# ChargerBase.net
KiCad netlist of a schematic drawn in EAGLE
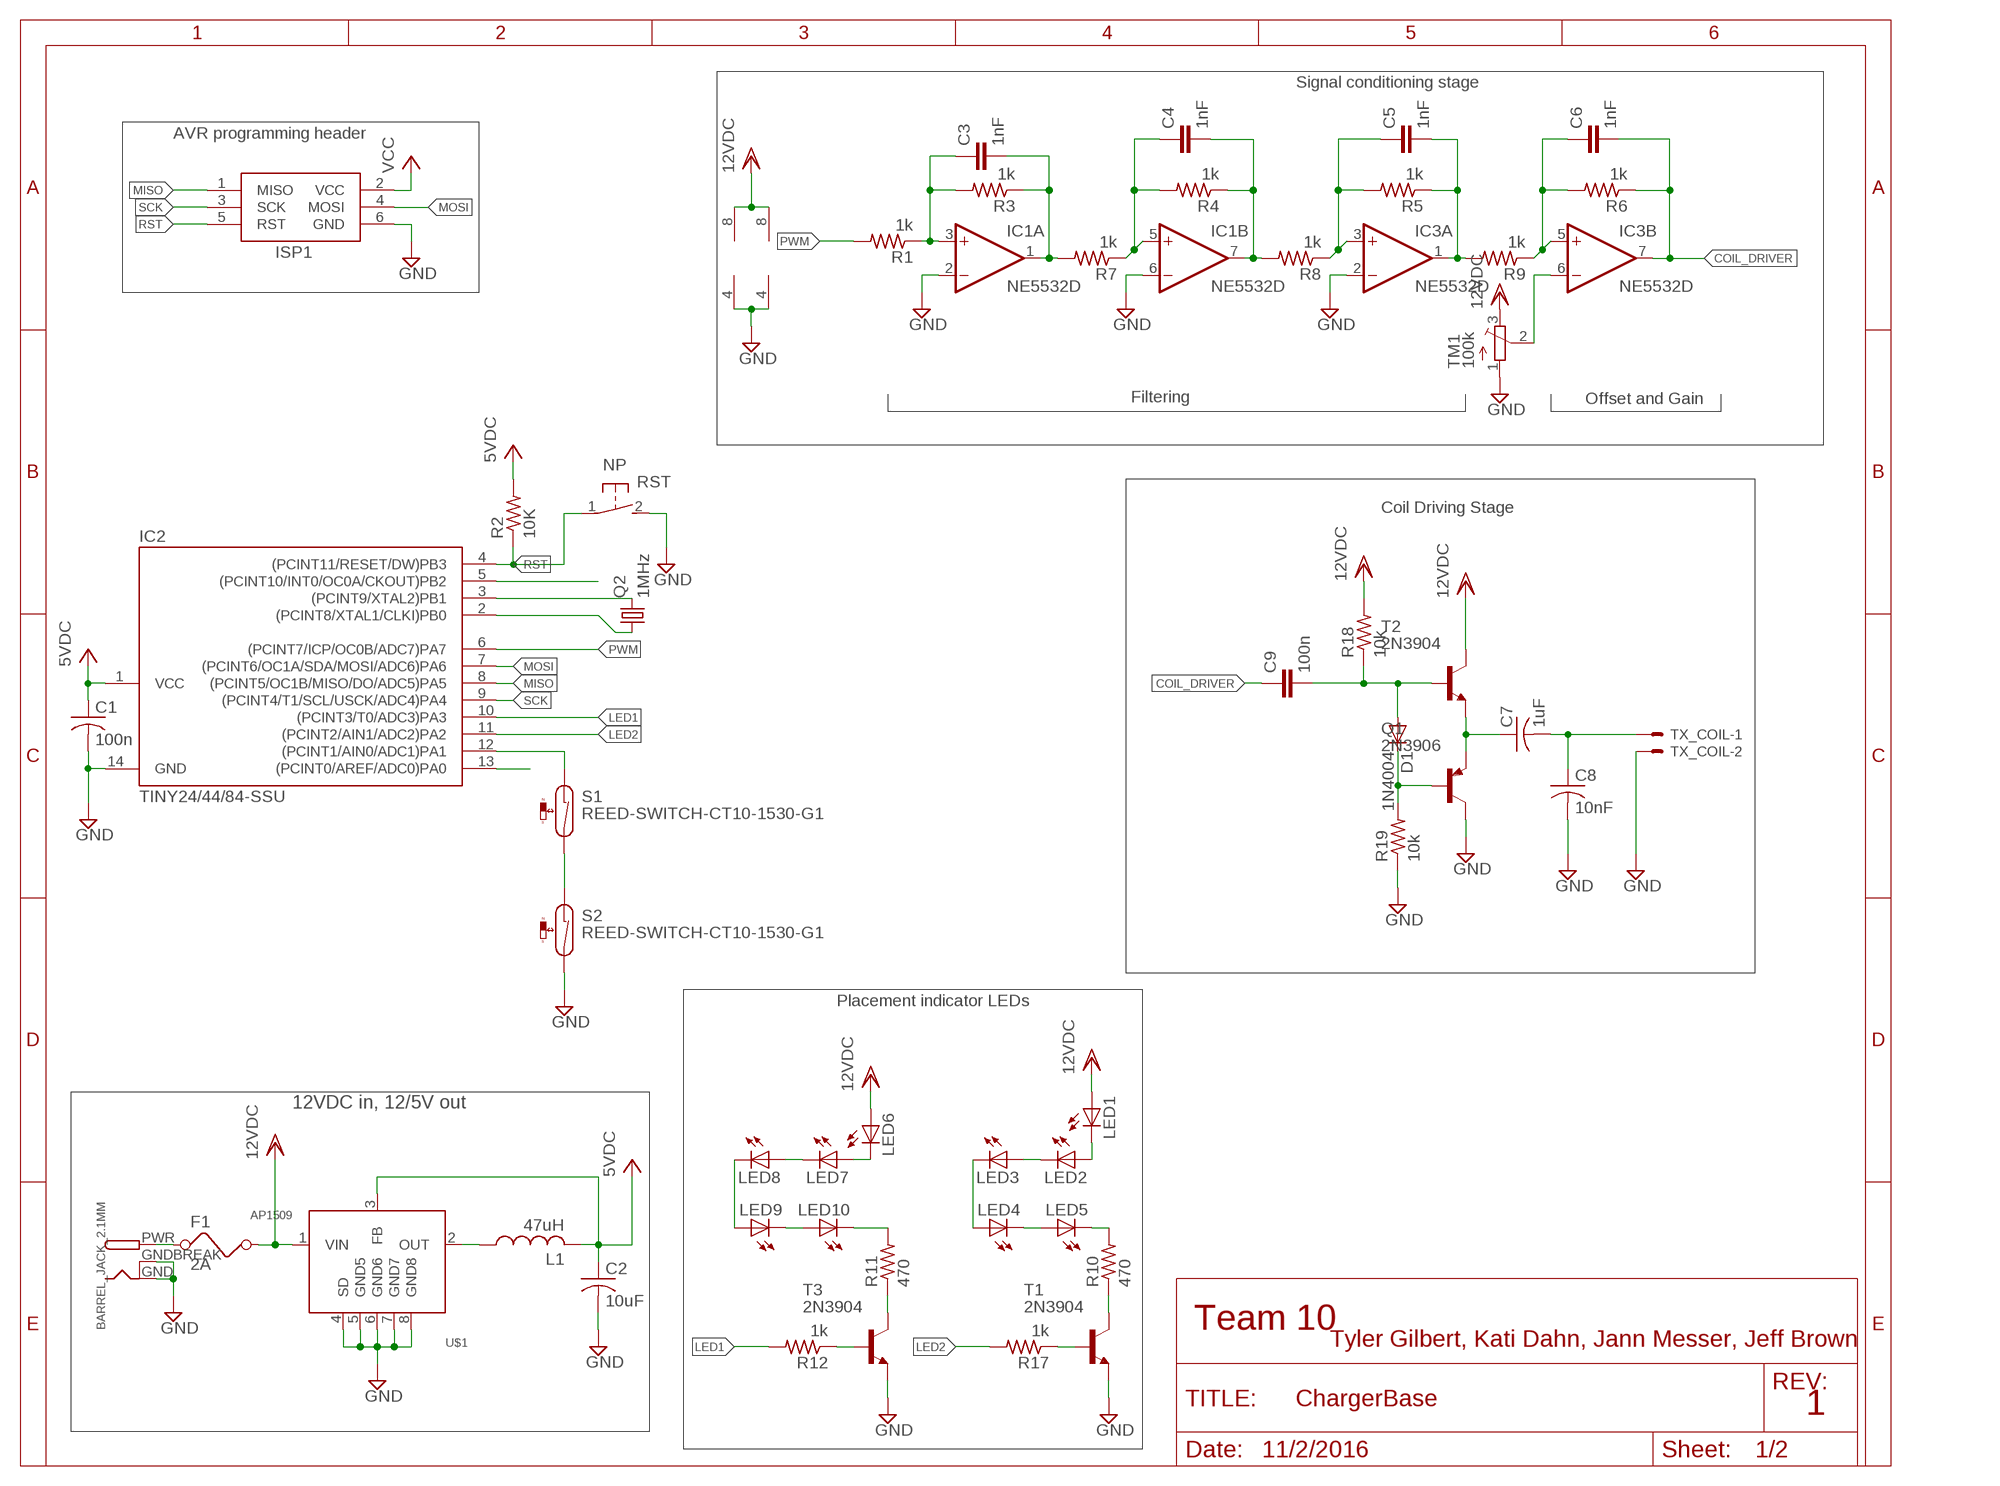
[diagram p0: schematic, sheet 1]

(export (version "E")
  (design (tool "Eeschema 10.0.6"))
  (components
    (comp (ref "BARREL_JACK_2.1MM")
      (value "DCBARRELPTH")
      (footprint "eagle-import:DCJACK_2MM_PTH")
      (libsource (lib "eagle-import") (part "DCBARRELPTH"))
    )
    (comp (ref "C1")
      (value "100n")
      (footprint "eagle-import:C0805")
      (libsource (lib "eagle-import") (part "rcl_C-USC0805"))
    )
    (comp (ref "C2")
      (value "10uF")
      (footprint "eagle-import:C025-040X050")
      (libsource (lib "eagle-import") (part "C-US025-040X050"))
    )
    (comp (ref "C3")
      (value "1nF")
      (footprint "eagle-import:C0805")
      (libsource (lib "eagle-import") (part "C-EUC0805"))
    )
    (comp (ref "C4")
      (value "1nF")
      (footprint "eagle-import:C0805")
      (libsource (lib "eagle-import") (part "C-EUC0805"))
    )
    (comp (ref "C5")
      (value "1nF")
      (footprint "eagle-import:C0805")
      (libsource (lib "eagle-import") (part "C-EUC0805"))
    )
    (comp (ref "C6")
      (value "1nF")
      (footprint "eagle-import:C0805")
      (libsource (lib "eagle-import") (part "C-EUC0805"))
    )
    (comp (ref "C7")
      (value "1uF")
      (footprint "eagle-import:C050-025X075")
      (libsource (lib "eagle-import") (part "C-US050-025X075"))
    )
    (comp (ref "C8")
      (value "10nF")
      (footprint "eagle-import:C050-025X075")
      (libsource (lib "eagle-import") (part "C-US050-025X075"))
    )
    (comp (ref "C9")
      (value "100n")
      (footprint "eagle-import:C0805")
      (libsource (lib "eagle-import") (part "C-EUC0805"))
    )
    (comp (ref "D1")
      (value "1N4004")
      (footprint "eagle-import:DO41-10")
      (libsource (lib "eagle-import") (part "1N4004"))
    )
    (comp (ref "F1")
      (value "2A")
      (footprint "eagle-import:FUSE")
      (libsource (lib "eagle-import") (part "FUSE"))
    )
    (comp (ref "IC1")
      (value "NE5532D")
      (footprint "eagle-import:SO08")
      (libsource (lib "eagle-import") (part "NE5532D"))
    )
    (comp (ref "IC2")
      (value "TINY24/44/84-SSU")
      (footprint "eagle-import:SOIC14")
      (libsource (lib "eagle-import") (part "TINY24/44/84-SSU"))
    )
    (comp (ref "IC3")
      (value "NE5532D")
      (footprint "eagle-import:SO08")
      (libsource (lib "eagle-import") (part "NE5532D"))
    )
    (comp (ref "ISP1")
      (value "AVRISP-6")
      (footprint "eagle-import:AVRISP")
      (libsource (lib "eagle-import") (part "AVRISP-6"))
    )
    (comp (ref "L1")
      (value "47uH")
      (footprint "eagle-import:0207_7")
      (libsource (lib "eagle-import") (part "L-US0207/7"))
    )
    (comp (ref "LED1")
      (value "LEDCHIPLED_0805")
      (footprint "eagle-import:CHIPLED_0805")
      (libsource (lib "eagle-import") (part "LEDCHIPLED_0805"))
    )
    (comp (ref "LED2")
      (value "LEDCHIPLED_0805")
      (footprint "eagle-import:CHIPLED_0805")
      (libsource (lib "eagle-import") (part "LEDCHIPLED_0805"))
    )
    (comp (ref "LED3")
      (value "LEDCHIPLED_0805")
      (footprint "eagle-import:CHIPLED_0805")
      (libsource (lib "eagle-import") (part "LEDCHIPLED_0805"))
    )
    (comp (ref "LED4")
      (value "LEDCHIPLED_0805")
      (footprint "eagle-import:CHIPLED_0805")
      (libsource (lib "eagle-import") (part "LEDCHIPLED_0805"))
    )
    (comp (ref "LED5")
      (value "LEDCHIPLED_0805")
      (footprint "eagle-import:CHIPLED_0805")
      (libsource (lib "eagle-import") (part "LEDCHIPLED_0805"))
    )
    (comp (ref "LED6")
      (value "LEDCHIPLED_0805")
      (footprint "eagle-import:CHIPLED_0805")
      (libsource (lib "eagle-import") (part "LEDCHIPLED_0805"))
    )
    (comp (ref "LED7")
      (value "LEDCHIPLED_0805")
      (footprint "eagle-import:CHIPLED_0805")
      (libsource (lib "eagle-import") (part "LEDCHIPLED_0805"))
    )
    (comp (ref "LED8")
      (value "LEDCHIPLED_0805")
      (footprint "eagle-import:CHIPLED_0805")
      (libsource (lib "eagle-import") (part "LEDCHIPLED_0805"))
    )
    (comp (ref "LED9")
      (value "LEDCHIPLED_0805")
      (footprint "eagle-import:CHIPLED_0805")
      (libsource (lib "eagle-import") (part "LEDCHIPLED_0805"))
    )
    (comp (ref "LED10")
      (value "LEDCHIPLED_0805")
      (footprint "eagle-import:CHIPLED_0805")
      (libsource (lib "eagle-import") (part "LEDCHIPLED_0805"))
    )
    (comp (ref "NP")
      (value "RST")
      (footprint "eagle-import:DTSM-3")
      (libsource (lib "eagle-import") (part "DTSM-3"))
    )
    (comp (ref "Q1")
      (value "2N3906")
      (footprint "eagle-import:TO92")
      (libsource (lib "eagle-import") (part "2N3906"))
    )
    (comp (ref "Q2")
      (value "1MHz")
      (footprint "eagle-import:SM49")
      (libsource (lib "eagle-import") (part "CRYSTALSM49"))
    )
    (comp (ref "R1")
      (value "1k")
      (footprint "eagle-import:R0805")
      (libsource (lib "eagle-import") (part "R-US_R0805"))
    )
    (comp (ref "R2")
      (value "10K")
      (footprint "eagle-import:R0805")
      (libsource (lib "eagle-import") (part "R-US_R0805"))
    )
    (comp (ref "R3")
      (value "1k")
      (footprint "eagle-import:R0805")
      (libsource (lib "eagle-import") (part "R-US_R0805"))
    )
    (comp (ref "R4")
      (value "1k")
      (footprint "eagle-import:R0805")
      (libsource (lib "eagle-import") (part "R-US_R0805"))
    )
    (comp (ref "R5")
      (value "1k")
      (footprint "eagle-import:R0805")
      (libsource (lib "eagle-import") (part "R-US_R0805"))
    )
    (comp (ref "R6")
      (value "1k")
      (footprint "eagle-import:R0805")
      (libsource (lib "eagle-import") (part "R-US_R0805"))
    )
    (comp (ref "R7")
      (value "1k")
      (footprint "eagle-import:R0805")
      (libsource (lib "eagle-import") (part "R-US_R0805"))
    )
    (comp (ref "R8")
      (value "1k")
      (footprint "eagle-import:R0805")
      (libsource (lib "eagle-import") (part "R-US_R0805"))
    )
    (comp (ref "R9")
      (value "1k")
      (footprint "eagle-import:R0805")
      (libsource (lib "eagle-import") (part "R-US_R0805"))
    )
    (comp (ref "R10")
      (value "470")
      (footprint "eagle-import:R0805")
      (libsource (lib "eagle-import") (part "R-US_R0805"))
    )
    (comp (ref "R11")
      (value "470")
      (footprint "eagle-import:R0805")
      (libsource (lib "eagle-import") (part "R-US_R0805"))
    )
    (comp (ref "R12")
      (value "1k")
      (footprint "eagle-import:R0805")
      (libsource (lib "eagle-import") (part "R-US_R0805"))
    )
    (comp (ref "R17")
      (value "1k")
      (footprint "eagle-import:R0805")
      (libsource (lib "eagle-import") (part "R-US_R0805"))
    )
    (comp (ref "R18")
      (value "10k")
      (footprint "eagle-import:R0805")
      (libsource (lib "eagle-import") (part "R-US_R0805"))
    )
    (comp (ref "R19")
      (value "10k")
      (footprint "eagle-import:R0805")
      (libsource (lib "eagle-import") (part "R-US_R0805"))
    )
    (comp (ref "S1")
      (value "REED-SWITCH-CT10-1530-G1")
      (footprint "eagle-import:CT10-G1")
      (fields (field (name "MF") "COTO TECHNOLOGY") (field (name "MPN") "CT10-1530-G1"))
      (libsource (lib "eagle-import") (part "REED-SWITCH-CT10-1530-G1"))
    )
    (comp (ref "S2")
      (value "REED-SWITCH-CT10-1530-G1")
      (footprint "eagle-import:CT10-G1")
      (fields (field (name "MF") "COTO TECHNOLOGY") (field (name "MPN") "CT10-1530-G1"))
      (libsource (lib "eagle-import") (part "REED-SWITCH-CT10-1530-G1"))
    )
    (comp (ref "T1")
      (value "2N3904")
      (footprint "eagle-import:TO92")
      (libsource (lib "eagle-import") (part "2N3904"))
    )
    (comp (ref "T2")
      (value "2N3904")
      (footprint "eagle-import:TO92")
      (libsource (lib "eagle-import") (part "2N3904"))
    )
    (comp (ref "T3")
      (value "2N3904")
      (footprint "eagle-import:TO92")
      (libsource (lib "eagle-import") (part "2N3904"))
    )
    (comp (ref "TM1")
      (value "100k")
      (footprint "eagle-import:TC33X")
      (libsource (lib "eagle-import") (part "TRIMPOTTC33X"))
    )
    (comp (ref "TX_COIL")
      (value "22-23-2021")
      (footprint "eagle-import:22-23-2021")
      (fields (field (name "MF") "MOLEX"))
      (libsource (lib "eagle-import") (part "22-23-2021"))
    )
    (comp (ref "U$1")
      (value "AP1509")
      (footprint "eagle-import:SOP08")
      (libsource (lib "eagle-import") (part "AP1509"))
    )
  )
  (nets
    (net (code "1") (name "5VDC") (class "Default")
      (node (ref "C1") (pin "1") (pinfunction "1_1") (pintype "passive"))
      (node (ref "C2") (pin "1") (pinfunction "1_1") (pintype "passive"))
      (node (ref "IC2") (pin "1") (pinfunction "VCC_1") (pintype "power_in"))
      (node (ref "ISP1") (pin "2") (pinfunction "VCC_2") (pintype "power_in"))
      (node (ref "L1") (pin "2") (pinfunction "2_2") (pintype "passive"))
      (node (ref "R2") (pin "2") (pinfunction "2_2") (pintype "passive"))
      (node (ref "U$1") (pin "3") (pinfunction "FB_3") (pintype "bidirectional"))
    )
    (net (code "2") (name "12VDC") (class "Default")
      (node (ref "F1") (pin "2") (pinfunction "2_2") (pintype "passive"))
      (node (ref "IC1") (pin "8") (pinfunction "V+_8") (pintype "power_in"))
      (node (ref "IC3") (pin "8") (pinfunction "V+_8") (pintype "power_in"))
      (node (ref "LED1") (pin "A") (pinfunction "A_A") (pintype "passive"))
      (node (ref "LED6") (pin "A") (pinfunction "A_A") (pintype "passive"))
      (node (ref "R18") (pin "2") (pinfunction "2_2") (pintype "passive"))
      (node (ref "T2") (pin "1") (pinfunction "C_1") (pintype "passive"))
      (node (ref "TM1") (pin "3") (pinfunction "E_3") (pintype "passive"))
      (node (ref "U$1") (pin "1") (pinfunction "VIN_1") (pintype "bidirectional"))
    )
    (net (code "3") (name "COIL_DRIVER") (class "Default")
      (node (ref "C6") (pin "2") (pinfunction "2_2") (pintype "passive"))
      (node (ref "C9") (pin "1") (pinfunction "1_1") (pintype "passive"))
      (node (ref "IC3") (pin "7") (pinfunction "OUT_7") (pintype "output"))
      (node (ref "R6") (pin "1") (pinfunction "1_1") (pintype "passive"))
    )
    (net (code "4") (name "GND") (class "Default")
      (node (ref "BARREL_JACK_2.1MM") (pin "GND") (pinfunction "GND_GND") (pintype "power_in"))
      (node (ref "BARREL_JACK_2.1MM") (pin "GNDBREAK") (pinfunction "GNDBREAK_GNDBREAK") (pintype "power_in"))
      (node (ref "C1") (pin "2") (pinfunction "2_2") (pintype "passive"))
      (node (ref "C2") (pin "2") (pinfunction "2_2") (pintype "passive"))
      (node (ref "C8") (pin "2") (pinfunction "2_2") (pintype "passive"))
      (node (ref "IC1") (pin "2") (pinfunction "-IN_2") (pintype "input"))
      (node (ref "IC1") (pin "4") (pinfunction "V-_4") (pintype "power_in"))
      (node (ref "IC1") (pin "6") (pinfunction "-IN_6") (pintype "input"))
      (node (ref "IC2") (pin "14") (pinfunction "GND_14") (pintype "power_in"))
      (node (ref "IC3") (pin "2") (pinfunction "-IN_2") (pintype "input"))
      (node (ref "IC3") (pin "4") (pinfunction "V-_4") (pintype "power_in"))
      (node (ref "ISP1") (pin "6") (pinfunction "GND_6") (pintype "power_in"))
      (node (ref "NP") (pin "2") (pinfunction "2_2") (pintype "passive"))
      (node (ref "Q1") (pin "1") (pinfunction "C_1") (pintype "passive"))
      (node (ref "R19") (pin "1") (pinfunction "1_1") (pintype "passive"))
      (node (ref "S2") (pin "2") (pinfunction "2_2") (pintype "passive"))
      (node (ref "T1") (pin "3") (pinfunction "E_3") (pintype "passive"))
      (node (ref "T3") (pin "3") (pinfunction "E_3") (pintype "passive"))
      (node (ref "TM1") (pin "1") (pinfunction "A_1") (pintype "passive"))
      (node (ref "TX_COIL") (pin "2") (pinfunction "S_2") (pintype "passive"))
      (node (ref "U$1") (pin "4") (pinfunction "SD_4") (pintype "bidirectional"))
      (node (ref "U$1") (pin "5") (pinfunction "GND5_5") (pintype "bidirectional"))
      (node (ref "U$1") (pin "6") (pinfunction "GND6_6") (pintype "bidirectional"))
      (node (ref "U$1") (pin "7") (pinfunction "GND7_7") (pintype "bidirectional"))
      (node (ref "U$1") (pin "8") (pinfunction "GND8_8") (pintype "bidirectional"))
    )
    (net (code "5") (name "LED1") (class "Default")
      (node (ref "IC2") (pin "10") (pinfunction "(PCINT3/T0/ADC3)PA3_10") (pintype "bidirectional"))
      (node (ref "R12") (pin "2") (pinfunction "2_2") (pintype "passive"))
    )
    (net (code "6") (name "LED2") (class "Default")
      (node (ref "IC2") (pin "11") (pinfunction "(PCINT2/AIN1/ADC2)PA2_11") (pintype "bidirectional"))
      (node (ref "R17") (pin "2") (pinfunction "2_2") (pintype "passive"))
    )
    (net (code "7") (name "MISO") (class "Default")
      (node (ref "IC2") (pin "8") (pinfunction "(PCINT5/OC1B/MISO/DO/ADC5)PA5_8") (pintype "bidirectional"))
      (node (ref "ISP1") (pin "1") (pinfunction "MISO_1") (pintype "input"))
    )
    (net (code "8") (name "MOSI") (class "Default")
      (node (ref "IC2") (pin "7") (pinfunction "(PCINT6/OC1A/SDA/MOSI/ADC6)PA6_7") (pintype "bidirectional"))
      (node (ref "ISP1") (pin "4") (pinfunction "MOSI_4") (pintype "output"))
    )
    (net (code "9") (name "Net-(BARREL_JACK_2.1MM-PadPWR)") (class "Default")
      (node (ref "BARREL_JACK_2.1MM") (pin "PWR") (pinfunction "PWR_PWR") (pintype "power_in"))
      (node (ref "F1") (pin "1") (pinfunction "1_1") (pintype "passive"))
    )
    (net (code "10") (name "Net-(IC1A-+IN)") (class "Default")
      (node (ref "C3") (pin "1") (pinfunction "1_1") (pintype "passive"))
      (node (ref "IC1") (pin "3") (pinfunction "+IN_3") (pintype "input"))
      (node (ref "R1") (pin "1") (pinfunction "1_1") (pintype "passive"))
      (node (ref "R3") (pin "2") (pinfunction "2_2") (pintype "passive"))
    )
    (net (code "11") (name "Net-(IC1A-OUT)") (class "Default")
      (node (ref "C3") (pin "2") (pinfunction "2_2") (pintype "passive"))
      (node (ref "IC1") (pin "1") (pinfunction "OUT_1") (pintype "output"))
      (node (ref "R3") (pin "1") (pinfunction "1_1") (pintype "passive"))
      (node (ref "R7") (pin "2") (pinfunction "2_2") (pintype "passive"))
    )
    (net (code "12") (name "Net-(IC1B-+IN)") (class "Default")
      (node (ref "C4") (pin "1") (pinfunction "1_1") (pintype "passive"))
      (node (ref "IC1") (pin "5") (pinfunction "+IN_5") (pintype "input"))
      (node (ref "R4") (pin "2") (pinfunction "2_2") (pintype "passive"))
      (node (ref "R7") (pin "1") (pinfunction "1_1") (pintype "passive"))
    )
    (net (code "13") (name "Net-(IC1B-OUT)") (class "Default")
      (node (ref "C4") (pin "2") (pinfunction "2_2") (pintype "passive"))
      (node (ref "IC1") (pin "7") (pinfunction "OUT_7") (pintype "output"))
      (node (ref "R4") (pin "1") (pinfunction "1_1") (pintype "passive"))
      (node (ref "R8") (pin "2") (pinfunction "2_2") (pintype "passive"))
    )
    (net (code "14") (name "Net-(IC2-(PCINT1{slash}AIN0{slash}ADC1)PA1)") (class "Default")
      (node (ref "IC2") (pin "12") (pinfunction "(PCINT1/AIN0/ADC1)PA1_12") (pintype "bidirectional"))
      (node (ref "S1") (pin "1") (pinfunction "1_1") (pintype "passive"))
    )
    (net (code "15") (name "Net-(IC2-(PCINT8{slash}XTAL1{slash}CLKI)PB0)") (class "Default")
      (node (ref "IC2") (pin "2") (pinfunction "(PCINT8/XTAL1/CLKI)PB0_2") (pintype "bidirectional"))
      (node (ref "Q2") (pin "1") (pinfunction "1_1") (pintype "passive"))
    )
    (net (code "16") (name "Net-(IC2-(PCINT9{slash}XTAL2)PB1)") (class "Default")
      (node (ref "IC2") (pin "3") (pinfunction "(PCINT9/XTAL2)PB1_3") (pintype "bidirectional"))
      (node (ref "Q2") (pin "2") (pinfunction "2_2") (pintype "passive"))
    )
    (net (code "17") (name "Net-(IC3A-+IN)") (class "Default")
      (node (ref "C5") (pin "1") (pinfunction "1_1") (pintype "passive"))
      (node (ref "IC3") (pin "3") (pinfunction "+IN_3") (pintype "input"))
      (node (ref "R5") (pin "2") (pinfunction "2_2") (pintype "passive"))
      (node (ref "R8") (pin "1") (pinfunction "1_1") (pintype "passive"))
    )
    (net (code "18") (name "Net-(IC3A-OUT)") (class "Default")
      (node (ref "C5") (pin "2") (pinfunction "2_2") (pintype "passive"))
      (node (ref "IC3") (pin "1") (pinfunction "OUT_1") (pintype "output"))
      (node (ref "R5") (pin "1") (pinfunction "1_1") (pintype "passive"))
      (node (ref "R9") (pin "2") (pinfunction "2_2") (pintype "passive"))
    )
    (net (code "19") (name "Net-(IC3B-+IN)") (class "Default")
      (node (ref "C6") (pin "1") (pinfunction "1_1") (pintype "passive"))
      (node (ref "IC3") (pin "5") (pinfunction "+IN_5") (pintype "input"))
      (node (ref "R6") (pin "2") (pinfunction "2_2") (pintype "passive"))
      (node (ref "R9") (pin "1") (pinfunction "1_1") (pintype "passive"))
    )
    (net (code "20") (name "Net-(IC3B--IN)") (class "Default")
      (node (ref "IC3") (pin "6") (pinfunction "-IN_6") (pintype "input"))
      (node (ref "TM1") (pin "2") (pinfunction "S_2") (pintype "passive"))
    )
    (net (code "21") (name "Net-(LED1-PadC)") (class "Default")
      (node (ref "LED1") (pin "C") (pinfunction "C_C") (pintype "passive"))
      (node (ref "LED2") (pin "A") (pinfunction "A_A") (pintype "passive"))
    )
    (net (code "22") (name "Net-(LED2-PadC)") (class "Default")
      (node (ref "LED2") (pin "C") (pinfunction "C_C") (pintype "passive"))
      (node (ref "LED3") (pin "A") (pinfunction "A_A") (pintype "passive"))
    )
    (net (code "23") (name "Net-(LED3-PadC)") (class "Default")
      (node (ref "LED3") (pin "C") (pinfunction "C_C") (pintype "passive"))
      (node (ref "LED4") (pin "A") (pinfunction "A_A") (pintype "passive"))
    )
    (net (code "24") (name "Net-(LED4-PadC)") (class "Default")
      (node (ref "LED4") (pin "C") (pinfunction "C_C") (pintype "passive"))
      (node (ref "LED5") (pin "A") (pinfunction "A_A") (pintype "passive"))
    )
    (net (code "25") (name "Net-(LED5-PadC)") (class "Default")
      (node (ref "LED5") (pin "C") (pinfunction "C_C") (pintype "passive"))
      (node (ref "R10") (pin "2") (pinfunction "2_2") (pintype "passive"))
    )
    (net (code "26") (name "Net-(LED6-PadC)") (class "Default")
      (node (ref "LED6") (pin "C") (pinfunction "C_C") (pintype "passive"))
      (node (ref "LED7") (pin "A") (pinfunction "A_A") (pintype "passive"))
    )
    (net (code "27") (name "Net-(LED7-PadC)") (class "Default")
      (node (ref "LED7") (pin "C") (pinfunction "C_C") (pintype "passive"))
      (node (ref "LED8") (pin "A") (pinfunction "A_A") (pintype "passive"))
    )
    (net (code "28") (name "Net-(LED8-PadC)") (class "Default")
      (node (ref "LED8") (pin "C") (pinfunction "C_C") (pintype "passive"))
      (node (ref "LED9") (pin "A") (pinfunction "A_A") (pintype "passive"))
    )
    (net (code "29") (name "Net-(LED10-PadA)") (class "Default")
      (node (ref "LED10") (pin "A") (pinfunction "A_A") (pintype "passive"))
      (node (ref "LED9") (pin "C") (pinfunction "C_C") (pintype "passive"))
    )
    (net (code "30") (name "Net-(LED10-PadC)") (class "Default")
      (node (ref "LED10") (pin "C") (pinfunction "C_C") (pintype "passive"))
      (node (ref "R11") (pin "2") (pinfunction "2_2") (pintype "passive"))
    )
    (net (code "31") (name "Net-(Q1-B)") (class "Default")
      (node (ref "D1") (pin "C") (pinfunction "C_C") (pintype "passive"))
      (node (ref "Q1") (pin "2") (pinfunction "B_2") (pintype "passive"))
      (node (ref "R19") (pin "2") (pinfunction "2_2") (pintype "passive"))
    )
    (net (code "32") (name "Net-(Q1-E)") (class "Default")
      (node (ref "C7") (pin "1") (pinfunction "1_1") (pintype "passive"))
      (node (ref "Q1") (pin "3") (pinfunction "E_3") (pintype "passive"))
      (node (ref "T2") (pin "3") (pinfunction "E_3") (pintype "passive"))
    )
    (net (code "33") (name "Net-(S1-Pad2)") (class "Default")
      (node (ref "S1") (pin "2") (pinfunction "2_2") (pintype "passive"))
      (node (ref "S2") (pin "1") (pinfunction "1_1") (pintype "passive"))
    )
    (net (code "34") (name "Net-(T1-B)") (class "Default")
      (node (ref "R17") (pin "1") (pinfunction "1_1") (pintype "passive"))
      (node (ref "T1") (pin "2") (pinfunction "B_2") (pintype "passive"))
    )
    (net (code "35") (name "Net-(T1-C)") (class "Default")
      (node (ref "R10") (pin "1") (pinfunction "1_1") (pintype "passive"))
      (node (ref "T1") (pin "1") (pinfunction "C_1") (pintype "passive"))
    )
    (net (code "36") (name "Net-(T2-B)") (class "Default")
      (node (ref "C9") (pin "2") (pinfunction "2_2") (pintype "passive"))
      (node (ref "D1") (pin "A") (pinfunction "A_A") (pintype "passive"))
      (node (ref "R18") (pin "1") (pinfunction "1_1") (pintype "passive"))
      (node (ref "T2") (pin "2") (pinfunction "B_2") (pintype "passive"))
    )
    (net (code "37") (name "Net-(T3-B)") (class "Default")
      (node (ref "R12") (pin "1") (pinfunction "1_1") (pintype "passive"))
      (node (ref "T3") (pin "2") (pinfunction "B_2") (pintype "passive"))
    )
    (net (code "38") (name "Net-(T3-C)") (class "Default")
      (node (ref "R11") (pin "1") (pinfunction "1_1") (pintype "passive"))
      (node (ref "T3") (pin "1") (pinfunction "C_1") (pintype "passive"))
    )
    (net (code "39") (name "Net-(TX_COILA-S)") (class "Default")
      (node (ref "C7") (pin "2") (pinfunction "2_2") (pintype "passive"))
      (node (ref "C8") (pin "1") (pinfunction "1_1") (pintype "passive"))
      (node (ref "TX_COIL") (pin "1") (pinfunction "S_1") (pintype "passive"))
    )
    (net (code "40") (name "Net-(U$1-OUT)") (class "Default")
      (node (ref "L1") (pin "1") (pinfunction "1_1") (pintype "passive"))
      (node (ref "U$1") (pin "2") (pinfunction "OUT_2") (pintype "bidirectional"))
    )
    (net (code "41") (name "PWM") (class "Default")
      (node (ref "IC2") (pin "6") (pinfunction "(PCINT7/ICP/OC0B/ADC7)PA7_6") (pintype "bidirectional"))
      (node (ref "R1") (pin "2") (pinfunction "2_2") (pintype "passive"))
    )
    (net (code "42") (name "RST") (class "Default")
      (node (ref "IC2") (pin "4") (pinfunction "(PCINT11/RESET/DW)PB3_4") (pintype "bidirectional"))
      (node (ref "ISP1") (pin "5") (pinfunction "RST_5") (pintype "output"))
      (node (ref "NP") (pin "1") (pinfunction "1_1") (pintype "passive"))
      (node (ref "R2") (pin "1") (pinfunction "1_1") (pintype "passive"))
    )
    (net (code "43") (name "SCK") (class "Default")
      (node (ref "IC2") (pin "9") (pinfunction "(PCINT4/T1/SCL/USCK/ADC4)PA4_9") (pintype "bidirectional"))
      (node (ref "ISP1") (pin "3") (pinfunction "SCK_3") (pintype "output"))
    )
    (net (code "44") (name "unconnected-(IC2-(PCINT0{slash}AREF{slash}ADC0)PA0-Pad13)") (class "Default")
      (node (ref "IC2") (pin "13") (pinfunction "(PCINT0/AREF/ADC0)PA0_13") (pintype "bidirectional"))
    )
    (net (code "45") (name "unconnected-(IC2-(PCINT10{slash}INT0{slash}OC0A{slash}CKOUT)PB2-Pad5)") (class "Default")
      (node (ref "IC2") (pin "5") (pinfunction "(PCINT10/INT0/OC0A/CKOUT)PB2_5") (pintype "bidirectional"))
    )
  )
)
